# lcd6.net
KiCad netlist of a schematic drawn in EAGLE
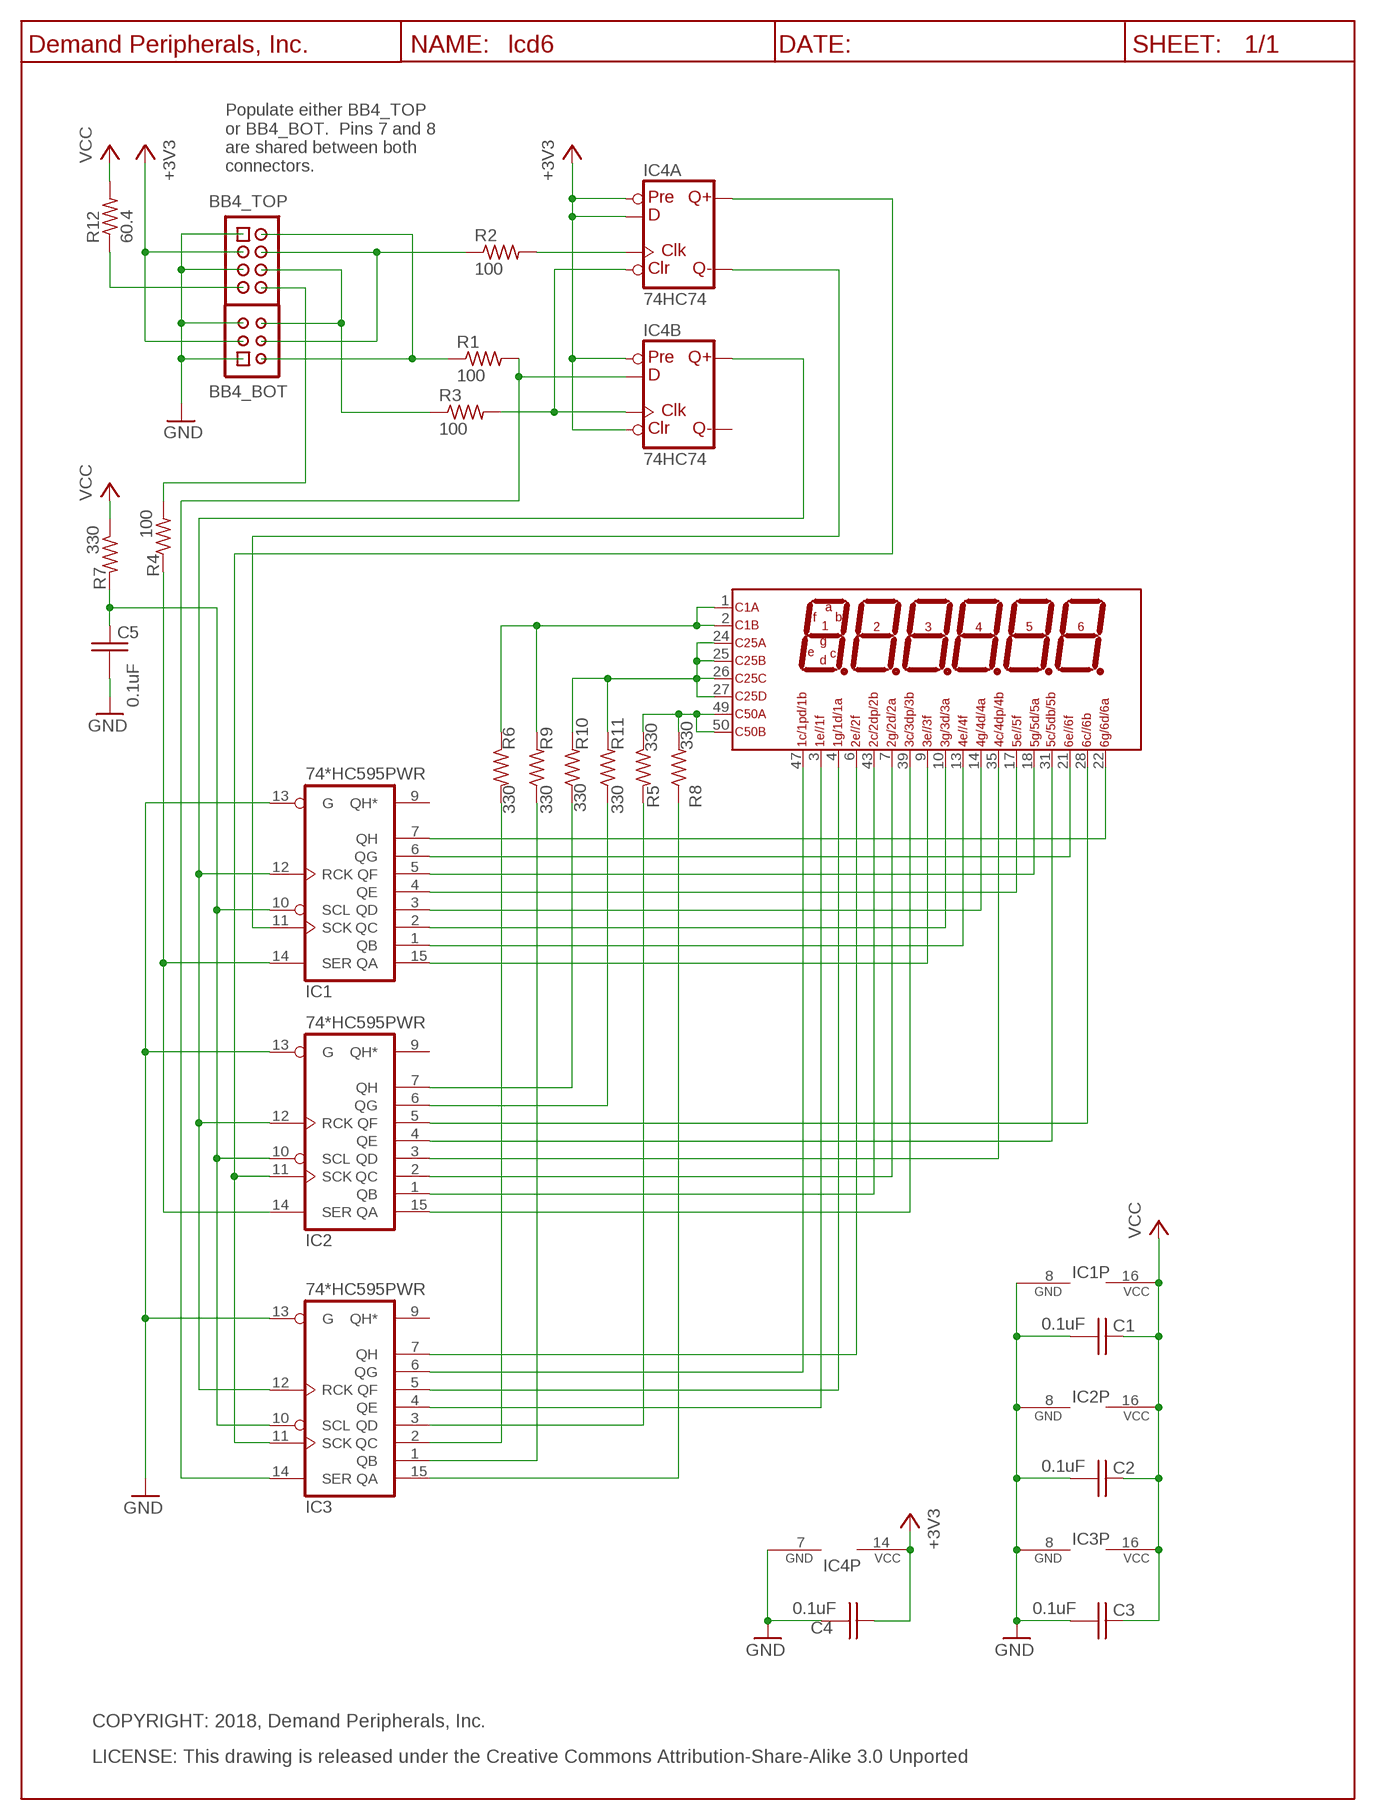
[diagram p0: schematic, sheet 1]

(export (version "E")
  (design (tool "Eeschema 10.0.6"))
  (components
    (comp (ref "BB4_BOT")
      (value "HDR-3X2")
      (footprint "eagle-import:HDR-3X2")
      (libsource (lib "eagle-import") (part "HDR-3X2"))
    )
    (comp (ref "BB4_TOP")
      (value "Keyed_Pin_Header_4x2(0.1\"x0.1\")")
      (footprint "eagle-import:HDR-4X2")
      (libsource (lib "eagle-import") (part "HDR-4X2-SHR"))
    )
    (comp (ref "C1")
      (value "0.1uF")
      (footprint "eagle-import:C0603")
      (libsource (lib "eagle-import") (part "C0.1UF_C0603"))
    )
    (comp (ref "C2")
      (value "0.1uF")
      (footprint "eagle-import:C0603")
      (libsource (lib "eagle-import") (part "C0.1UF_C0603"))
    )
    (comp (ref "C3")
      (value "0.1uF")
      (footprint "eagle-import:C0603")
      (libsource (lib "eagle-import") (part "C0.1UF_C0603"))
    )
    (comp (ref "C4")
      (value "0.1uF")
      (footprint "eagle-import:C0603")
      (libsource (lib "eagle-import") (part "C0.1UF_C0603"))
    )
    (comp (ref "C5")
      (value "0.1uF")
      (footprint "eagle-import:C0603")
      (libsource (lib "eagle-import") (part "C0.1UF_C0603"))
    )
    (comp (ref "DISP1")
      (value "LCD6")
      (footprint "eagle-import:LCD6")
      (libsource (lib "eagle-import") (part "LCD6"))
    )
    (comp (ref "IC1")
      (value "74*HC595PWR")
      (footprint "eagle-import:SO16")
      (libsource (lib "eagle-import") (part "74595"))
    )
    (comp (ref "IC2")
      (value "74*HC595PWR")
      (footprint "eagle-import:SO16")
      (libsource (lib "eagle-import") (part "74595"))
    )
    (comp (ref "IC3")
      (value "74*HC595PWR")
      (footprint "eagle-import:SO16")
      (libsource (lib "eagle-import") (part "74595"))
    )
    (comp (ref "IC4")
      (value "74HC74")
      (footprint "eagle-import:SO14")
      (libsource (lib "eagle-import") (part "74AHC74SS"))
    )
    (comp (ref "R1")
      (value "100")
      (footprint "eagle-import:R0603")
      (libsource (lib "eagle-import") (part "R100_R0603"))
    )
    (comp (ref "R2")
      (value "100")
      (footprint "eagle-import:R0603")
      (libsource (lib "eagle-import") (part "R100_R0603"))
    )
    (comp (ref "R3")
      (value "100")
      (footprint "eagle-import:R0603")
      (libsource (lib "eagle-import") (part "R100_R0603"))
    )
    (comp (ref "R4")
      (value "100")
      (footprint "eagle-import:R0603")
      (libsource (lib "eagle-import") (part "R100_R0603"))
    )
    (comp (ref "R5")
      (value "330")
      (footprint "eagle-import:R0603")
      (libsource (lib "eagle-import") (part "R330_R0603"))
    )
    (comp (ref "R6")
      (value "330")
      (footprint "eagle-import:R0603")
      (libsource (lib "eagle-import") (part "R330_R0603"))
    )
    (comp (ref "R7")
      (value "330")
      (footprint "eagle-import:R0603")
      (libsource (lib "eagle-import") (part "R330_R0603"))
    )
    (comp (ref "R8")
      (value "330")
      (footprint "eagle-import:R0603")
      (libsource (lib "eagle-import") (part "R330_R0603"))
    )
    (comp (ref "R9")
      (value "330")
      (footprint "eagle-import:R0603")
      (libsource (lib "eagle-import") (part "R330_R0603"))
    )
    (comp (ref "R10")
      (value "330")
      (footprint "eagle-import:R0603")
      (libsource (lib "eagle-import") (part "R330_R0603"))
    )
    (comp (ref "R11")
      (value "330")
      (footprint "eagle-import:R0603")
      (libsource (lib "eagle-import") (part "R330_R0603"))
    )
    (comp (ref "R12")
      (value "60.4")
      (footprint "eagle-import:R0603")
      (libsource (lib "eagle-import") (part "R60.4_R0603"))
    )
    (comp (ref "U$1")
      (value "DP_FRAME_P")
      (footprint "eagle-import:P_FRAME")
      (libsource (lib "eagle-import") (part "DP_FRAME_P"))
    )
  )
  (nets
    (net (code "1") (name "+3V3") (class "Default")
      (node (ref "BB4_BOT") (pin "3") (pinfunction "3_3") (pintype "passive"))
      (node (ref "BB4_TOP") (pin "3") (pinfunction "3_3") (pintype "passive"))
      (node (ref "C4") (pin "1") (pinfunction "1_1") (pintype "passive"))
      (node (ref "IC4") (pin "10") (pinfunction "PRE_10") (pintype "input"))
      (node (ref "IC4") (pin "13") (pinfunction "CLR_13") (pintype "input"))
      (node (ref "IC4") (pin "14") (pinfunction "VCC_14") (pintype "power_in"))
      (node (ref "IC4") (pin "2") (pinfunction "D_2") (pintype "input"))
      (node (ref "IC4") (pin "4") (pinfunction "PRE_4") (pintype "input"))
    )
    (net (code "2") (name "GND") (class "Default")
      (node (ref "BB4_BOT") (pin "1") (pinfunction "1_1") (pintype "passive"))
      (node (ref "BB4_BOT") (pin "5") (pinfunction "5_5") (pintype "passive"))
      (node (ref "BB4_TOP") (pin "1") (pinfunction "1_1") (pintype "passive"))
      (node (ref "BB4_TOP") (pin "5") (pinfunction "5_5") (pintype "passive"))
      (node (ref "C1") (pin "2") (pinfunction "2_2") (pintype "passive"))
      (node (ref "C2") (pin "2") (pinfunction "2_2") (pintype "passive"))
      (node (ref "C3") (pin "2") (pinfunction "2_2") (pintype "passive"))
      (node (ref "C4") (pin "2") (pinfunction "2_2") (pintype "passive"))
      (node (ref "C5") (pin "2") (pinfunction "2_2") (pintype "passive"))
      (node (ref "IC1") (pin "13") (pinfunction "G_13") (pintype "input"))
      (node (ref "IC1") (pin "8") (pinfunction "GND_8") (pintype "power_in"))
      (node (ref "IC2") (pin "13") (pinfunction "G_13") (pintype "input"))
      (node (ref "IC2") (pin "8") (pinfunction "GND_8") (pintype "power_in"))
      (node (ref "IC3") (pin "13") (pinfunction "G_13") (pintype "input"))
      (node (ref "IC3") (pin "8") (pinfunction "GND_8") (pintype "power_in"))
      (node (ref "IC4") (pin "7") (pinfunction "GND_7") (pintype "power_in"))
    )
    (net (code "3") (name "Net-(BB4_BOT-Pad2)") (class "Default")
      (node (ref "BB4_BOT") (pin "2") (pinfunction "2_2") (pintype "passive"))
      (node (ref "BB4_TOP") (pin "2") (pinfunction "2_2") (pintype "passive"))
      (node (ref "R1") (pin "1") (pinfunction "1_1") (pintype "passive"))
    )
    (net (code "4") (name "Net-(BB4_BOT-Pad4)") (class "Default")
      (node (ref "BB4_BOT") (pin "4") (pinfunction "4_4") (pintype "passive"))
      (node (ref "BB4_TOP") (pin "4") (pinfunction "4_4") (pintype "passive"))
      (node (ref "R2") (pin "1") (pinfunction "1_1") (pintype "passive"))
    )
    (net (code "5") (name "Net-(BB4_BOT-Pad6)") (class "Default")
      (node (ref "BB4_BOT") (pin "6") (pinfunction "6_6") (pintype "passive"))
      (node (ref "BB4_TOP") (pin "6") (pinfunction "6_6") (pintype "passive"))
      (node (ref "R3") (pin "1") (pinfunction "1_1") (pintype "passive"))
    )
    (net (code "6") (name "Net-(BB4_TOP-Pad7)") (class "Default")
      (node (ref "BB4_TOP") (pin "7") (pinfunction "7_7") (pintype "passive"))
      (node (ref "R12") (pin "1") (pinfunction "1_1") (pintype "passive"))
    )
    (net (code "7") (name "Net-(BB4_TOP-Pad8)") (class "Default")
      (node (ref "BB4_TOP") (pin "8") (pinfunction "8_8") (pintype "passive"))
      (node (ref "R4") (pin "2") (pinfunction "2_2") (pintype "passive"))
    )
    (net (code "8") (name "Net-(DISP1-Pad1)") (class "Default")
      (node (ref "DISP1") (pin "1") (pinfunction "1_1") (pintype "passive"))
      (node (ref "DISP1") (pin "2") (pinfunction "2_2") (pintype "passive"))
      (node (ref "R6") (pin "1") (pinfunction "1_1") (pintype "passive"))
      (node (ref "R9") (pin "2") (pinfunction "2_2") (pintype "passive"))
    )
    (net (code "9") (name "Net-(DISP1-Pad24)") (class "Default")
      (node (ref "DISP1") (pin "24") (pinfunction "24_24") (pintype "passive"))
      (node (ref "DISP1") (pin "25") (pinfunction "25_25") (pintype "passive"))
      (node (ref "DISP1") (pin "26") (pinfunction "26_26") (pintype "passive"))
      (node (ref "DISP1") (pin "27") (pinfunction "27_27") (pintype "passive"))
      (node (ref "R10") (pin "2") (pinfunction "2_2") (pintype "passive"))
      (node (ref "R11") (pin "2") (pinfunction "2_2") (pintype "passive"))
    )
    (net (code "10") (name "Net-(DISP1-Pad49)") (class "Default")
      (node (ref "DISP1") (pin "49") (pinfunction "49_49") (pintype "passive"))
      (node (ref "DISP1") (pin "50") (pinfunction "50_50") (pintype "passive"))
      (node (ref "R5") (pin "1") (pinfunction "1_1") (pintype "passive"))
      (node (ref "R8") (pin "2") (pinfunction "2_2") (pintype "passive"))
    )
    (net (code "11") (name "Net-(IC1A-QA)") (class "Default")
      (node (ref "DISP1") (pin "9") (pinfunction "9_9") (pintype "passive"))
      (node (ref "IC1") (pin "15") (pinfunction "QA_15") (pintype "tri_state"))
    )
    (net (code "12") (name "Net-(IC1A-QB)") (class "Default")
      (node (ref "DISP1") (pin "13") (pinfunction "13_13") (pintype "passive"))
      (node (ref "IC1") (pin "1") (pinfunction "QB_1") (pintype "tri_state"))
    )
    (net (code "13") (name "Net-(IC1A-QC)") (class "Default")
      (node (ref "DISP1") (pin "10") (pinfunction "10_10") (pintype "passive"))
      (node (ref "IC1") (pin "2") (pinfunction "QC_2") (pintype "tri_state"))
    )
    (net (code "14") (name "Net-(IC1A-QD)") (class "Default")
      (node (ref "DISP1") (pin "14") (pinfunction "14_14") (pintype "passive"))
      (node (ref "IC1") (pin "3") (pinfunction "QD_3") (pintype "tri_state"))
    )
    (net (code "15") (name "Net-(IC1A-QE)") (class "Default")
      (node (ref "DISP1") (pin "17") (pinfunction "17_17") (pintype "passive"))
      (node (ref "IC1") (pin "4") (pinfunction "QE_4") (pintype "tri_state"))
    )
    (net (code "16") (name "Net-(IC1A-QF)") (class "Default")
      (node (ref "DISP1") (pin "18") (pinfunction "18_18") (pintype "passive"))
      (node (ref "IC1") (pin "5") (pinfunction "QF_5") (pintype "tri_state"))
    )
    (net (code "17") (name "Net-(IC1A-QG)") (class "Default")
      (node (ref "DISP1") (pin "21") (pinfunction "21_21") (pintype "passive"))
      (node (ref "IC1") (pin "6") (pinfunction "QG_6") (pintype "tri_state"))
    )
    (net (code "18") (name "Net-(IC1A-QH)") (class "Default")
      (node (ref "DISP1") (pin "22") (pinfunction "22_22") (pintype "passive"))
      (node (ref "IC1") (pin "7") (pinfunction "QH_7") (pintype "tri_state"))
    )
    (net (code "19") (name "Net-(IC1A-RCK)") (class "Default")
      (node (ref "IC1") (pin "12") (pinfunction "RCK_12") (pintype "input"))
      (node (ref "IC2") (pin "12") (pinfunction "RCK_12") (pintype "input"))
      (node (ref "IC3") (pin "12") (pinfunction "RCK_12") (pintype "input"))
      (node (ref "IC4") (pin "9") (pinfunction "Q_9") (pintype "output"))
    )
    (net (code "20") (name "Net-(IC1A-SCK)") (class "Default")
      (node (ref "IC1") (pin "11") (pinfunction "SCK_11") (pintype "input"))
      (node (ref "IC4") (pin "6") (pinfunction "~{Q}_6") (pintype "output"))
    )
    (net (code "21") (name "Net-(IC1A-SCL)") (class "Default")
      (node (ref "C5") (pin "1") (pinfunction "1_1") (pintype "passive"))
      (node (ref "IC1") (pin "10") (pinfunction "SCL_10") (pintype "input"))
      (node (ref "IC2") (pin "10") (pinfunction "SCL_10") (pintype "input"))
      (node (ref "IC3") (pin "10") (pinfunction "SCL_10") (pintype "input"))
      (node (ref "R7") (pin "2") (pinfunction "2_2") (pintype "passive"))
    )
    (net (code "22") (name "Net-(IC1A-SER)") (class "Default")
      (node (ref "IC1") (pin "14") (pinfunction "SER_14") (pintype "input"))
      (node (ref "IC2") (pin "14") (pinfunction "SER_14") (pintype "input"))
      (node (ref "R4") (pin "1") (pinfunction "1_1") (pintype "passive"))
    )
    (net (code "23") (name "Net-(IC2A-QA)") (class "Default")
      (node (ref "DISP1") (pin "39") (pinfunction "39_39") (pintype "passive"))
      (node (ref "IC2") (pin "15") (pinfunction "QA_15") (pintype "tri_state"))
    )
    (net (code "24") (name "Net-(IC2A-QB)") (class "Default")
      (node (ref "DISP1") (pin "43") (pinfunction "43_43") (pintype "passive"))
      (node (ref "IC2") (pin "1") (pinfunction "QB_1") (pintype "tri_state"))
    )
    (net (code "25") (name "Net-(IC2A-QC)") (class "Default")
      (node (ref "DISP1") (pin "7") (pinfunction "7_7") (pintype "passive"))
      (node (ref "IC2") (pin "2") (pinfunction "QC_2") (pintype "tri_state"))
    )
    (net (code "26") (name "Net-(IC2A-QD)") (class "Default")
      (node (ref "DISP1") (pin "35") (pinfunction "35_35") (pintype "passive"))
      (node (ref "IC2") (pin "3") (pinfunction "QD_3") (pintype "tri_state"))
    )
    (net (code "27") (name "Net-(IC2A-QE)") (class "Default")
      (node (ref "DISP1") (pin "31") (pinfunction "31_31") (pintype "passive"))
      (node (ref "IC2") (pin "4") (pinfunction "QE_4") (pintype "tri_state"))
    )
    (net (code "28") (name "Net-(IC2A-QF)") (class "Default")
      (node (ref "DISP1") (pin "28") (pinfunction "28_28") (pintype "passive"))
      (node (ref "IC2") (pin "5") (pinfunction "QF_5") (pintype "tri_state"))
    )
    (net (code "29") (name "Net-(IC2A-QG)") (class "Default")
      (node (ref "IC2") (pin "6") (pinfunction "QG_6") (pintype "tri_state"))
      (node (ref "R11") (pin "1") (pinfunction "1_1") (pintype "passive"))
    )
    (net (code "30") (name "Net-(IC2A-QH)") (class "Default")
      (node (ref "IC2") (pin "7") (pinfunction "QH_7") (pintype "tri_state"))
      (node (ref "R10") (pin "1") (pinfunction "1_1") (pintype "passive"))
    )
    (net (code "31") (name "Net-(IC2A-SCK)") (class "Default")
      (node (ref "IC2") (pin "11") (pinfunction "SCK_11") (pintype "input"))
      (node (ref "IC3") (pin "11") (pinfunction "SCK_11") (pintype "input"))
      (node (ref "IC4") (pin "5") (pinfunction "Q_5") (pintype "output"))
    )
    (net (code "32") (name "Net-(IC3A-QA)") (class "Default")
      (node (ref "IC3") (pin "15") (pinfunction "QA_15") (pintype "tri_state"))
      (node (ref "R8") (pin "1") (pinfunction "1_1") (pintype "passive"))
    )
    (net (code "33") (name "Net-(IC3A-QB)") (class "Default")
      (node (ref "IC3") (pin "1") (pinfunction "QB_1") (pintype "tri_state"))
      (node (ref "R9") (pin "1") (pinfunction "1_1") (pintype "passive"))
    )
    (net (code "34") (name "Net-(IC3A-QC)") (class "Default")
      (node (ref "IC3") (pin "2") (pinfunction "QC_2") (pintype "tri_state"))
      (node (ref "R6") (pin "2") (pinfunction "2_2") (pintype "passive"))
    )
    (net (code "35") (name "Net-(IC3A-QD)") (class "Default")
      (node (ref "IC3") (pin "3") (pinfunction "QD_3") (pintype "tri_state"))
      (node (ref "R5") (pin "2") (pinfunction "2_2") (pintype "passive"))
    )
    (net (code "36") (name "Net-(IC3A-QE)") (class "Default")
      (node (ref "DISP1") (pin "3") (pinfunction "3_3") (pintype "passive"))
      (node (ref "IC3") (pin "4") (pinfunction "QE_4") (pintype "tri_state"))
    )
    (net (code "37") (name "Net-(IC3A-QF)") (class "Default")
      (node (ref "DISP1") (pin "4") (pinfunction "4_4") (pintype "passive"))
      (node (ref "IC3") (pin "5") (pinfunction "QF_5") (pintype "tri_state"))
    )
    (net (code "38") (name "Net-(IC3A-QG)") (class "Default")
      (node (ref "DISP1") (pin "47") (pinfunction "47_47") (pintype "passive"))
      (node (ref "IC3") (pin "6") (pinfunction "QG_6") (pintype "tri_state"))
    )
    (net (code "39") (name "Net-(IC3A-QH)") (class "Default")
      (node (ref "DISP1") (pin "6") (pinfunction "6_6") (pintype "passive"))
      (node (ref "IC3") (pin "7") (pinfunction "QH_7") (pintype "tri_state"))
    )
    (net (code "40") (name "Net-(IC3A-SER)") (class "Default")
      (node (ref "IC3") (pin "14") (pinfunction "SER_14") (pintype "input"))
      (node (ref "IC4") (pin "12") (pinfunction "D_12") (pintype "input"))
      (node (ref "R1") (pin "2") (pinfunction "2_2") (pintype "passive"))
    )
    (net (code "41") (name "Net-(IC4A-CLK)") (class "Default")
      (node (ref "IC4") (pin "3") (pinfunction "CLK_3") (pintype "input"))
      (node (ref "R2") (pin "2") (pinfunction "2_2") (pintype "passive"))
    )
    (net (code "42") (name "Net-(IC4A-CLR)") (class "Default")
      (node (ref "IC4") (pin "1") (pinfunction "CLR_1") (pintype "input"))
      (node (ref "IC4") (pin "11") (pinfunction "CLK_11") (pintype "input"))
      (node (ref "R3") (pin "2") (pinfunction "2_2") (pintype "passive"))
    )
    (net (code "43") (name "VCC") (class "Default")
      (node (ref "C1") (pin "1") (pinfunction "1_1") (pintype "passive"))
      (node (ref "C2") (pin "1") (pinfunction "1_1") (pintype "passive"))
      (node (ref "C3") (pin "1") (pinfunction "1_1") (pintype "passive"))
      (node (ref "IC1") (pin "16") (pinfunction "VCC_16") (pintype "power_in"))
      (node (ref "IC2") (pin "16") (pinfunction "VCC_16") (pintype "power_in"))
      (node (ref "IC3") (pin "16") (pinfunction "VCC_16") (pintype "power_in"))
      (node (ref "R12") (pin "2") (pinfunction "2_2") (pintype "passive"))
      (node (ref "R7") (pin "1") (pinfunction "1_1") (pintype "passive"))
    )
    (net (code "44") (name "unconnected-(IC1A-QH*-Pad9)") (class "Default")
      (node (ref "IC1") (pin "9") (pinfunction "QH*_9") (pintype "tri_state"))
    )
    (net (code "45") (name "unconnected-(IC2A-QH*-Pad9)") (class "Default")
      (node (ref "IC2") (pin "9") (pinfunction "QH*_9") (pintype "tri_state"))
    )
    (net (code "46") (name "unconnected-(IC3A-QH*-Pad9)") (class "Default")
      (node (ref "IC3") (pin "9") (pinfunction "QH*_9") (pintype "tri_state"))
    )
    (net (code "47") (name "unconnected-(IC4B-~{Q}-Pad8)") (class "Default")
      (node (ref "IC4") (pin "8") (pinfunction "~{Q}_8") (pintype "output"))
    )
  )
)
